# Module_20200404_0_7SigDisplay.net
KiCad netlist of a schematic drawn in EAGLE
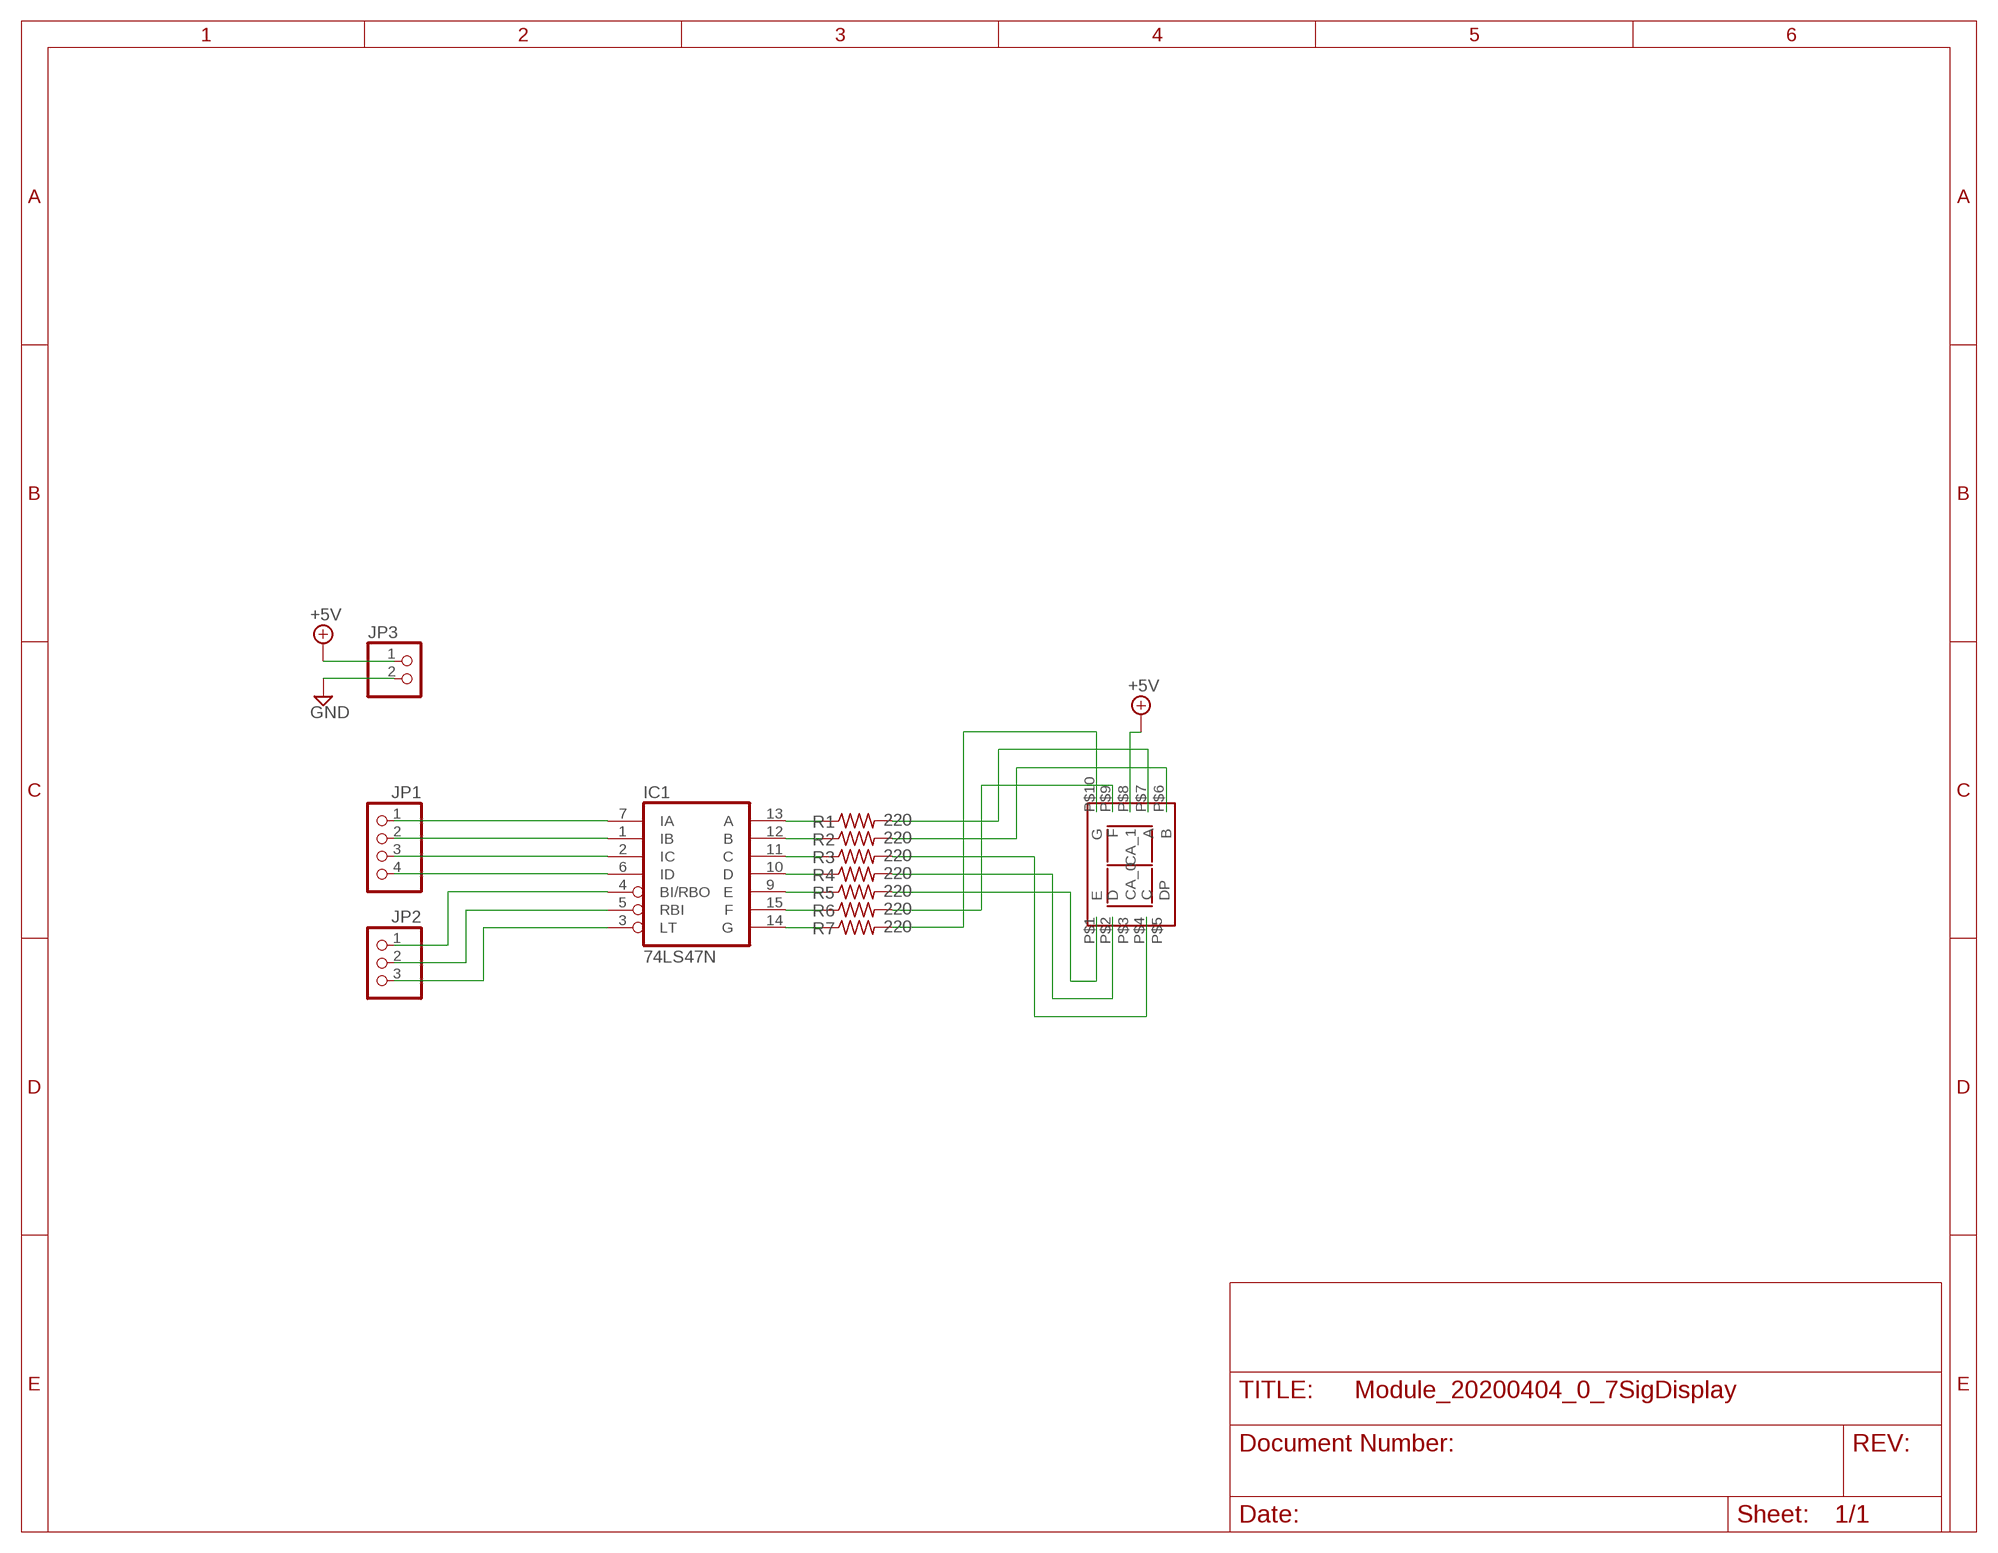
[diagram p0: schematic, sheet 1]

(export (version "E")
  (design (tool "Eeschema 10.0.6"))
  (components
    (comp (ref "IC1")
      (value "74LS47N")
      (footprint "eagle-import:DIL16")
      (libsource (lib "eagle-import") (part "7447NLS"))
    )
    (comp (ref "JP1")
      (value "PINHD-1X4")
      (footprint "eagle-import:1X04")
      (libsource (lib "eagle-import") (part "PINHD-1X4"))
    )
    (comp (ref "JP2")
      (value "PINHD-1X3")
      (footprint "eagle-import:1X03")
      (libsource (lib "eagle-import") (part "PINHD-1X3"))
    )
    (comp (ref "JP3")
      (value "PINHD-1X2")
      (footprint "eagle-import:1X02")
      (libsource (lib "eagle-import") (part "PINHD-1X2"))
    )
    (comp (ref "R1")
      (value "220")
      (footprint "eagle-import:0207_12")
      (libsource (lib "eagle-import") (part "R-US_0207/12"))
    )
    (comp (ref "R2")
      (value "220")
      (footprint "eagle-import:0207_12")
      (libsource (lib "eagle-import") (part "R-US_0207/12"))
    )
    (comp (ref "R3")
      (value "220")
      (footprint "eagle-import:0207_12")
      (libsource (lib "eagle-import") (part "R-US_0207/12"))
    )
    (comp (ref "R4")
      (value "220")
      (footprint "eagle-import:0207_12")
      (libsource (lib "eagle-import") (part "R-US_0207/12"))
    )
    (comp (ref "R5")
      (value "220")
      (footprint "eagle-import:0207_12")
      (libsource (lib "eagle-import") (part "R-US_0207/12"))
    )
    (comp (ref "R6")
      (value "220")
      (footprint "eagle-import:0207_12")
      (libsource (lib "eagle-import") (part "R-US_0207/12"))
    )
    (comp (ref "R7")
      (value "220")
      (footprint "eagle-import:0207_12")
      (libsource (lib "eagle-import") (part "R-US_0207/12"))
    )
    (comp (ref "U$1")
      (value "CSS-516E")
      (footprint "eagle-import:CSS-516E")
      (libsource (lib "eagle-import") (part "CSS-516E"))
    )
  )
  (nets
    (net (code "1") (name "+5V") (class "Default")
      (node (ref "JP3") (pin "1") (pinfunction "1_1") (pintype "passive"))
      (node (ref "U$1") (pin "P$8") (pinfunction "CA_1_P$8") (pintype "power_in"))
    )
    (net (code "2") (name "/CA_0") (class "Default")
      (node (ref "U$1") (pin "P$3") (pinfunction "CA_0_P$3") (pintype "power_in"))
    )
    (net (code "3") (name "GND") (class "Default")
      (node (ref "JP3") (pin "2") (pinfunction "2_2") (pintype "passive"))
    )
    (net (code "4") (name "Net-(IC1A-A)") (class "Default")
      (node (ref "IC1") (pin "13") (pinfunction "A_13") (pintype "output"))
      (node (ref "R1") (pin "1") (pinfunction "1_1") (pintype "passive"))
    )
    (net (code "5") (name "Net-(IC1A-B)") (class "Default")
      (node (ref "IC1") (pin "12") (pinfunction "B_12") (pintype "output"))
      (node (ref "R2") (pin "1") (pinfunction "1_1") (pintype "passive"))
    )
    (net (code "6") (name "Net-(IC1A-BI{slash}RBO)") (class "Default")
      (node (ref "IC1") (pin "4") (pinfunction "BI/RBO_4") (pintype "input"))
      (node (ref "JP2") (pin "1") (pinfunction "1_1") (pintype "passive"))
    )
    (net (code "7") (name "Net-(IC1A-C)") (class "Default")
      (node (ref "IC1") (pin "11") (pinfunction "C_11") (pintype "output"))
      (node (ref "R3") (pin "1") (pinfunction "1_1") (pintype "passive"))
    )
    (net (code "8") (name "Net-(IC1A-D)") (class "Default")
      (node (ref "IC1") (pin "10") (pinfunction "D_10") (pintype "output"))
      (node (ref "R4") (pin "1") (pinfunction "1_1") (pintype "passive"))
    )
    (net (code "9") (name "Net-(IC1A-E)") (class "Default")
      (node (ref "IC1") (pin "9") (pinfunction "E_9") (pintype "output"))
      (node (ref "R5") (pin "1") (pinfunction "1_1") (pintype "passive"))
    )
    (net (code "10") (name "Net-(IC1A-F)") (class "Default")
      (node (ref "IC1") (pin "15") (pinfunction "F_15") (pintype "output"))
      (node (ref "R6") (pin "1") (pinfunction "1_1") (pintype "passive"))
    )
    (net (code "11") (name "Net-(IC1A-G)") (class "Default")
      (node (ref "IC1") (pin "14") (pinfunction "G_14") (pintype "output"))
      (node (ref "R7") (pin "1") (pinfunction "1_1") (pintype "passive"))
    )
    (net (code "12") (name "Net-(IC1A-IA)") (class "Default")
      (node (ref "IC1") (pin "7") (pinfunction "IA_7") (pintype "input"))
      (node (ref "JP1") (pin "1") (pinfunction "1_1") (pintype "passive"))
    )
    (net (code "13") (name "Net-(IC1A-IB)") (class "Default")
      (node (ref "IC1") (pin "1") (pinfunction "IB_1") (pintype "input"))
      (node (ref "JP1") (pin "2") (pinfunction "2_2") (pintype "passive"))
    )
    (net (code "14") (name "Net-(IC1A-IC)") (class "Default")
      (node (ref "IC1") (pin "2") (pinfunction "IC_2") (pintype "input"))
      (node (ref "JP1") (pin "3") (pinfunction "3_3") (pintype "passive"))
    )
    (net (code "15") (name "Net-(IC1A-ID)") (class "Default")
      (node (ref "IC1") (pin "6") (pinfunction "ID_6") (pintype "input"))
      (node (ref "JP1") (pin "4") (pinfunction "4_4") (pintype "passive"))
    )
    (net (code "16") (name "Net-(IC1A-LT)") (class "Default")
      (node (ref "IC1") (pin "3") (pinfunction "LT_3") (pintype "input"))
      (node (ref "JP2") (pin "3") (pinfunction "3_3") (pintype "passive"))
    )
    (net (code "17") (name "Net-(IC1A-RBI)") (class "Default")
      (node (ref "IC1") (pin "5") (pinfunction "RBI_5") (pintype "input"))
      (node (ref "JP2") (pin "2") (pinfunction "2_2") (pintype "passive"))
    )
    (net (code "18") (name "Net-(U$1-A)") (class "Default")
      (node (ref "R1") (pin "2") (pinfunction "2_2") (pintype "passive"))
      (node (ref "U$1") (pin "P$7") (pinfunction "A_P$7") (pintype "input"))
    )
    (net (code "19") (name "Net-(U$1-B)") (class "Default")
      (node (ref "R2") (pin "2") (pinfunction "2_2") (pintype "passive"))
      (node (ref "U$1") (pin "P$6") (pinfunction "B_P$6") (pintype "input"))
    )
    (net (code "20") (name "Net-(U$1-C)") (class "Default")
      (node (ref "R3") (pin "2") (pinfunction "2_2") (pintype "passive"))
      (node (ref "U$1") (pin "P$4") (pinfunction "C_P$4") (pintype "input"))
    )
    (net (code "21") (name "Net-(U$1-D)") (class "Default")
      (node (ref "R4") (pin "2") (pinfunction "2_2") (pintype "passive"))
      (node (ref "U$1") (pin "P$2") (pinfunction "D_P$2") (pintype "input"))
    )
    (net (code "22") (name "Net-(U$1-E)") (class "Default")
      (node (ref "R5") (pin "2") (pinfunction "2_2") (pintype "passive"))
      (node (ref "U$1") (pin "P$1") (pinfunction "E_P$1") (pintype "input"))
    )
    (net (code "23") (name "Net-(U$1-F)") (class "Default")
      (node (ref "R6") (pin "2") (pinfunction "2_2") (pintype "passive"))
      (node (ref "U$1") (pin "P$9") (pinfunction "F_P$9") (pintype "input"))
    )
    (net (code "24") (name "Net-(U$1-G)") (class "Default")
      (node (ref "R7") (pin "2") (pinfunction "2_2") (pintype "passive"))
      (node (ref "U$1") (pin "P$10") (pinfunction "G_P$10") (pintype "input"))
    )
    (net (code "25") (name "unconnected-(U$1-DP-PadP$5)") (class "Default")
      (node (ref "U$1") (pin "P$5") (pinfunction "DP_P$5") (pintype "input"))
    )
  )
)
